# Connectors.net
KiCad netlist of a schematic drawn in Altium Designer
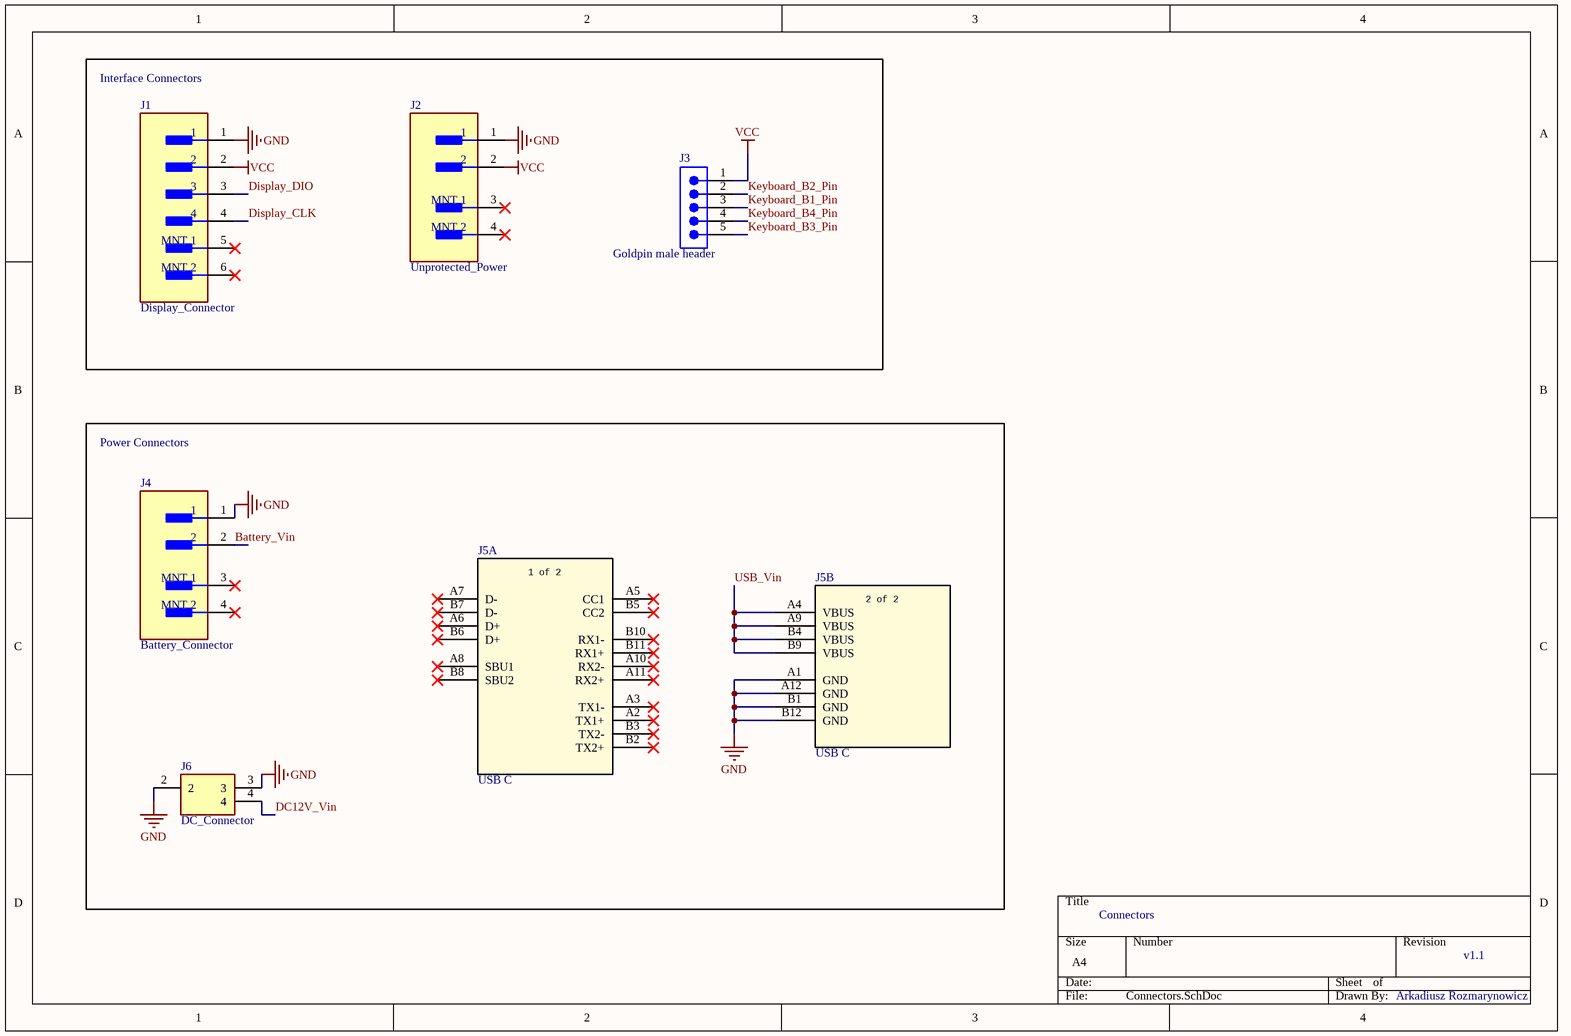
[diagram p0: Connectors.SchDoc]

(export (version "E")
  (design (tool "Eeschema 10.0.6"))
  (components
    (comp (ref "J1")
      (value "Display_Connector")
      (footprint "FP-BM04B-GHS-TBT_LF_SN-MFG")
      (description "CONN HEADER SMD 4POS 1.25MM")
      (libsource (lib "Altium Content Vault") (part "8e3688c4b118bffc0dd9b7401e414ba"))
    )
    (comp (ref "J2")
      (value "Unprotected_Power")
      (footprint "FP-SM02B-GHS-TB_LF_SN-MFG")
      (description "CONN HEADER SMD R/A 2POS 1.25MM")
      (libsource (lib "Altium Content Vault") (part "56ec3178a87b3978bdc1b3682cd516a"))
    )
    (comp (ref "J3")
      (value "Goldpin male header")
      (footprint "SMTC-MTLW-105-05-X-S-190")
      (fields (field (name "MANUFACTURER") "Samtec") (field (name "PARTNUMBER") "MTLW-105-05-T-S-190"))
      (libsource (lib "Altium Content Vault") (part "SMTC-MTLW-105-05-X-S-190"))
    )
    (comp (ref "J4")
      (value "Battery_Connector")
      (footprint "FP-SM02B-GHS-TB_LF_SN-MFG")
      (description "CONN HEADER SMD R/A 2POS 1.25MM")
      (libsource (lib "Altium Content Vault") (part "56ec3178a87b3978bdc1b3682cd516a"))
    )
    (comp (ref "J5")
      (value "USB C")
      (footprint "CONN_1054500101_MOL")
      (fields
        (field (name "MANUFACTURER_PART_NUMBER") "1054500101")
        (field (name "COPYRIGHT") "Copyright (C) 2026 Ultra Librarian. All rights reserved.")
      )
      (libsource (lib "MOLEX_1054500101") (part "1054500101"))
    )
    (comp (ref "J6")
      (value "DC_Connector")
      (footprint "PCGK21")
      (description "Socket; DC supply; male; 5.5/2.1mm; 5.5mm; 2.1mm; THT; angled 90")
      (fields (field (name "MANUFACTURER_PART_NUMBER") "PC-GK2.1"))
      (libsource (lib "PC-GK2_1") (part "PC-GK2.1"))
    )
  )
  (nets
    (net (code "1") (name "/Battery_Vin") (class "Default")
      (node (ref "J4") (pin "2") (pinfunction "2_2") (pintype "passive"))
    )
    (net (code "2") (name "/DC12V_Vin") (class "Default")
      (node (ref "J6") (pin "4") (pinfunction "4_4") (pintype "passive"))
    )
    (net (code "3") (name "/Display_CLK") (class "Default")
      (node (ref "J1") (pin "4") (pinfunction "4_4") (pintype "passive"))
    )
    (net (code "4") (name "/Display_DIO") (class "Default")
      (node (ref "J1") (pin "3") (pinfunction "3_3") (pintype "passive"))
    )
    (net (code "5") (name "/Keyboard_B1_Pin") (class "Default")
      (node (ref "J3") (pin "3") (pinfunction "3_3") (pintype "passive"))
    )
    (net (code "6") (name "/Keyboard_B2_Pin") (class "Default")
      (node (ref "J3") (pin "2") (pinfunction "2_2") (pintype "passive"))
    )
    (net (code "7") (name "/Keyboard_B3_Pin") (class "Default")
      (node (ref "J3") (pin "5") (pinfunction "5_5") (pintype "passive"))
    )
    (net (code "8") (name "/Keyboard_B4_Pin") (class "Default")
      (node (ref "J3") (pin "4") (pinfunction "4_4") (pintype "passive"))
    )
    (net (code "9") (name "/USB_Vin") (class "Default")
      (node (ref "J5") (pin "A4") (pinfunction "VBUS_A4") (pintype "power_in"))
      (node (ref "J5") (pin "A9") (pinfunction "VBUS_A9") (pintype "power_in"))
      (node (ref "J5") (pin "B4") (pinfunction "VBUS_B4") (pintype "power_in"))
      (node (ref "J5") (pin "B9") (pinfunction "VBUS_B9") (pintype "power_in"))
    )
    (net (code "10") (name "GND") (class "Default")
      (node (ref "J1") (pin "1") (pinfunction "1_1") (pintype "passive"))
      (node (ref "J2") (pin "1") (pinfunction "1_1") (pintype "passive"))
      (node (ref "J4") (pin "1") (pinfunction "1_1") (pintype "passive"))
      (node (ref "J5") (pin "A1") (pinfunction "GND_A1") (pintype "power_in"))
      (node (ref "J5") (pin "A12") (pinfunction "GND_A12") (pintype "power_in"))
      (node (ref "J5") (pin "B1") (pinfunction "GND_B1") (pintype "power_in"))
      (node (ref "J5") (pin "B12") (pinfunction "GND_B12") (pintype "power_in"))
      (node (ref "J6") (pin "2") (pinfunction "2_2") (pintype "passive"))
      (node (ref "J6") (pin "3") (pinfunction "3_3") (pintype "passive"))
    )
    (net (code "11") (name "VCC") (class "Default")
      (node (ref "J1") (pin "2") (pinfunction "2_2") (pintype "passive"))
      (node (ref "J2") (pin "2") (pinfunction "2_2") (pintype "passive"))
      (node (ref "J3") (pin "1") (pinfunction "1_1") (pintype "passive"))
    )
    (net (code "12") (name "unconnected-(J1-MNT_1-Pad5)") (class "Default")
      (node (ref "J1") (pin "5") (pinfunction "MNT_1_5") (pintype "passive+no_connect"))
    )
    (net (code "13") (name "unconnected-(J1-MNT_2-Pad6)") (class "Default")
      (node (ref "J1") (pin "6") (pinfunction "MNT_2_6") (pintype "passive+no_connect"))
    )
    (net (code "14") (name "unconnected-(J2-MNT_1-Pad3)") (class "Default")
      (node (ref "J2") (pin "3") (pinfunction "MNT_1_3") (pintype "passive+no_connect"))
    )
    (net (code "15") (name "unconnected-(J2-MNT_2-Pad4)") (class "Default")
      (node (ref "J2") (pin "4") (pinfunction "MNT_2_4") (pintype "passive+no_connect"))
    )
    (net (code "16") (name "unconnected-(J4-MNT_1-Pad3)") (class "Default")
      (node (ref "J4") (pin "3") (pinfunction "MNT_1_3") (pintype "passive+no_connect"))
    )
    (net (code "17") (name "unconnected-(J4-MNT_2-Pad4)") (class "Default")
      (node (ref "J4") (pin "4") (pinfunction "MNT_2_4") (pintype "passive+no_connect"))
    )
    (net (code "18") (name "unconnected-(J5A-CC1-PadA5)") (class "Default")
      (node (ref "J5") (pin "A5") (pinfunction "CC1_A5") (pintype "passive+no_connect"))
    )
    (net (code "19") (name "unconnected-(J5A-CC2-PadB5)") (class "Default")
      (node (ref "J5") (pin "B5") (pinfunction "CC2_B5") (pintype "passive+no_connect"))
    )
    (net (code "20") (name "unconnected-(J5A-D+-PadA6)") (class "Default")
      (node (ref "J5") (pin "A6") (pinfunction "D+_A6") (pintype "passive+no_connect"))
    )
    (net (code "21") (name "unconnected-(J5A-D+-PadB6)") (class "Default")
      (node (ref "J5") (pin "B6") (pinfunction "D+_B6") (pintype "passive+no_connect"))
    )
    (net (code "22") (name "unconnected-(J5A-D--PadA7)") (class "Default")
      (node (ref "J5") (pin "A7") (pinfunction "D-_A7") (pintype "passive+no_connect"))
    )
    (net (code "23") (name "unconnected-(J5A-D--PadB7)") (class "Default")
      (node (ref "J5") (pin "B7") (pinfunction "D-_B7") (pintype "passive+no_connect"))
    )
    (net (code "24") (name "unconnected-(J5A-RX1+-PadB11)") (class "Default")
      (node (ref "J5") (pin "B11") (pinfunction "RX1+_B11") (pintype "passive+no_connect"))
    )
    (net (code "25") (name "unconnected-(J5A-RX1--PadB10)") (class "Default")
      (node (ref "J5") (pin "B10") (pinfunction "RX1-_B10") (pintype "passive+no_connect"))
    )
    (net (code "26") (name "unconnected-(J5A-RX2+-PadA11)") (class "Default")
      (node (ref "J5") (pin "A11") (pinfunction "RX2+_A11") (pintype "passive+no_connect"))
    )
    (net (code "27") (name "unconnected-(J5A-RX2--PadA10)") (class "Default")
      (node (ref "J5") (pin "A10") (pinfunction "RX2-_A10") (pintype "passive+no_connect"))
    )
    (net (code "28") (name "unconnected-(J5A-SBU1-PadA8)") (class "Default")
      (node (ref "J5") (pin "A8") (pinfunction "SBU1_A8") (pintype "passive+no_connect"))
    )
    (net (code "29") (name "unconnected-(J5A-SBU2-PadB8)") (class "Default")
      (node (ref "J5") (pin "B8") (pinfunction "SBU2_B8") (pintype "passive+no_connect"))
    )
    (net (code "30") (name "unconnected-(J5A-TX1+-PadA2)") (class "Default")
      (node (ref "J5") (pin "A2") (pinfunction "TX1+_A2") (pintype "passive+no_connect"))
    )
    (net (code "31") (name "unconnected-(J5A-TX1--PadA3)") (class "Default")
      (node (ref "J5") (pin "A3") (pinfunction "TX1-_A3") (pintype "passive+no_connect"))
    )
    (net (code "32") (name "unconnected-(J5A-TX2+-PadB2)") (class "Default")
      (node (ref "J5") (pin "B2") (pinfunction "TX2+_B2") (pintype "passive+no_connect"))
    )
    (net (code "33") (name "unconnected-(J5A-TX2--PadB3)") (class "Default")
      (node (ref "J5") (pin "B3") (pinfunction "TX2-_B3") (pintype "passive+no_connect"))
    )
  )
)
